# mcu.net
KiCad netlist of a schematic drawn in Altium Designer
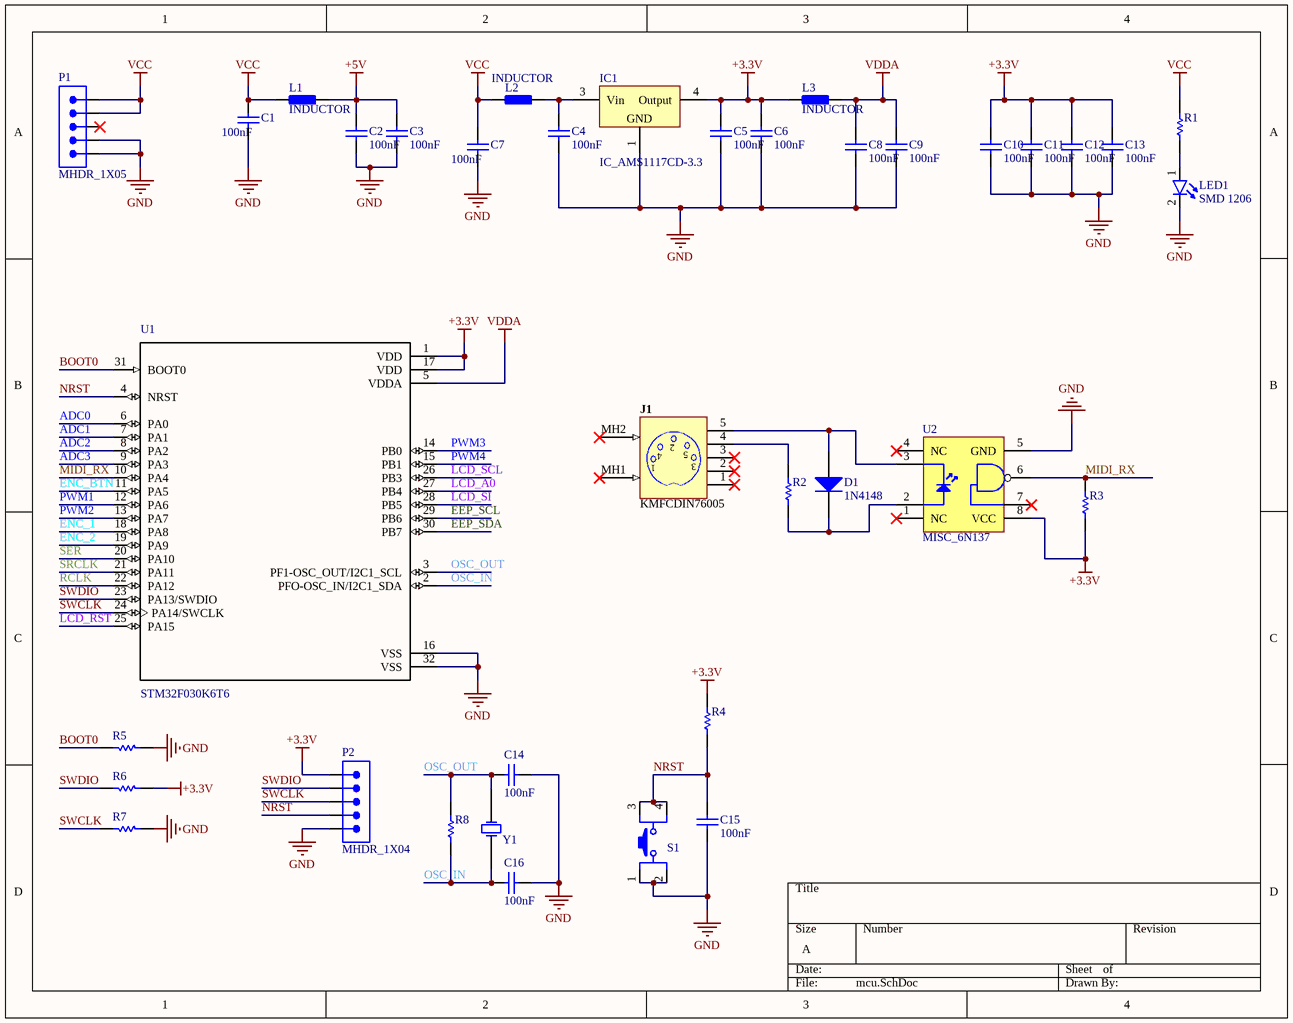
[diagram p0: mcu.SchDoc]

(export (version "E")
  (design (tool "Eeschema 10.0.6"))
  (components
    (comp (ref "C1")
      (value "100nF")
      (footprint "CAPC3216M (1206)")
      (description "Bipolar Capacitor")
      (fields
        (field (name "VOLTAGE") "100V")
        (field (name "DESIGNER") "Eng. Saeid Jorablo")
        (field (name "PUBLISHER") "SJ Unlimited")
      )
      (libsource (lib "SJ Passive Components") (part "CAP_Bipolar"))
    )
    (comp (ref "C2")
      (value "100nF")
      (footprint "CAPC3216M (1206)")
      (description "Bipolar Capacitor")
      (fields
        (field (name "VOLTAGE") "100V")
        (field (name "DESIGNER") "Eng. Saeid Jorablo")
        (field (name "PUBLISHER") "SJ Unlimited")
      )
      (libsource (lib "SJ Passive Components") (part "CAP_Bipolar"))
    )
    (comp (ref "C3")
      (value "100nF")
      (footprint "CAPC3216M (1206)")
      (description "Bipolar Capacitor")
      (fields
        (field (name "VOLTAGE") "100V")
        (field (name "Comment") "1uF")
        (field (name "DESIGNER") "Eng. Saeid Jorablo")
        (field (name "PUBLISHER") "SJ Unlimited")
      )
      (libsource (lib "SJ Passive Components") (part "CAP_Bipolar"))
    )
    (comp (ref "C4")
      (value "100nF")
      (footprint "CAPC3216M (1206)")
      (description "Bipolar Capacitor")
      (fields
        (field (name "VOLTAGE") "100V")
        (field (name "DESIGNER") "Eng. Saeid Jorablo")
        (field (name "PUBLISHER") "SJ Unlimited")
      )
      (libsource (lib "SJ Passive Components") (part "CAP_Bipolar"))
    )
    (comp (ref "C5")
      (value "100nF")
      (footprint "CAPC3216M (1206)")
      (description "Bipolar Capacitor")
      (fields
        (field (name "VOLTAGE") "100V")
        (field (name "DESIGNER") "Eng. Saeid Jorablo")
        (field (name "PUBLISHER") "SJ Unlimited")
      )
      (libsource (lib "SJ Passive Components") (part "CAP_Bipolar"))
    )
    (comp (ref "C6")
      (value "100nF")
      (footprint "CAPC3216M (1206)")
      (description "Bipolar Capacitor")
      (fields
        (field (name "VOLTAGE") "100V")
        (field (name "DESIGNER") "Eng. Saeid Jorablo")
        (field (name "PUBLISHER") "SJ Unlimited")
      )
      (libsource (lib "SJ Passive Components") (part "CAP_Bipolar"))
    )
    (comp (ref "C7")
      (value "100nF")
      (footprint "CAPC3216M (1206)")
      (description "Bipolar Capacitor")
      (fields
        (field (name "VOLTAGE") "100V")
        (field (name "DESIGNER") "Eng. Saeid Jorablo")
        (field (name "PUBLISHER") "SJ Unlimited")
      )
      (libsource (lib "SJ Passive Components") (part "CAP_Bipolar"))
    )
    (comp (ref "C8")
      (value "100nF")
      (footprint "CAPC3216M (1206)")
      (description "Bipolar Capacitor")
      (fields
        (field (name "VOLTAGE") "100V")
        (field (name "DESIGNER") "Eng. Saeid Jorablo")
        (field (name "PUBLISHER") "SJ Unlimited")
      )
      (libsource (lib "SJ Passive Components") (part "CAP_Bipolar"))
    )
    (comp (ref "C9")
      (value "100nF")
      (footprint "CAPC3216M (1206)")
      (description "Bipolar Capacitor")
      (fields
        (field (name "VOLTAGE") "100V")
        (field (name "Comment") "1uF")
        (field (name "DESIGNER") "Eng. Saeid Jorablo")
        (field (name "PUBLISHER") "SJ Unlimited")
      )
      (libsource (lib "SJ Passive Components") (part "CAP_Bipolar"))
    )
    (comp (ref "C10")
      (value "100nF")
      (footprint "CAPC3216M (1206)")
      (description "Bipolar Capacitor")
      (fields
        (field (name "VOLTAGE") "100V")
        (field (name "DESIGNER") "Eng. Saeid Jorablo")
        (field (name "PUBLISHER") "SJ Unlimited")
      )
      (libsource (lib "SJ Passive Components") (part "CAP_Bipolar"))
    )
    (comp (ref "C11")
      (value "100nF")
      (footprint "CAPC3216M (1206)")
      (description "Bipolar Capacitor")
      (fields
        (field (name "VOLTAGE") "100V")
        (field (name "DESIGNER") "Eng. Saeid Jorablo")
        (field (name "PUBLISHER") "SJ Unlimited")
      )
      (libsource (lib "SJ Passive Components") (part "CAP_Bipolar"))
    )
    (comp (ref "C12")
      (value "100nF")
      (footprint "CAPC3216M (1206)")
      (description "Bipolar Capacitor")
      (fields
        (field (name "VOLTAGE") "100V")
        (field (name "DESIGNER") "Eng. Saeid Jorablo")
        (field (name "PUBLISHER") "SJ Unlimited")
      )
      (libsource (lib "SJ Passive Components") (part "CAP_Bipolar"))
    )
    (comp (ref "C13")
      (value "100nF")
      (footprint "CAPC3216M (1206)")
      (description "Bipolar Capacitor")
      (fields
        (field (name "VOLTAGE") "100V")
        (field (name "DESIGNER") "Eng. Saeid Jorablo")
        (field (name "PUBLISHER") "SJ Unlimited")
      )
      (libsource (lib "SJ Passive Components") (part "CAP_Bipolar"))
    )
    (comp (ref "C14")
      (value "100nF")
      (footprint "CAPC3216M (1206)")
      (description "Bipolar Capacitor")
      (fields
        (field (name "VOLTAGE") "100V")
        (field (name "DESIGNER") "Eng. Saeid Jorablo")
        (field (name "PUBLISHER") "SJ Unlimited")
      )
      (libsource (lib "SJ Passive Components") (part "CAP_Bipolar"))
    )
    (comp (ref "C15")
      (value "100nF")
      (footprint "CAPC3216M (1206)")
      (description "Bipolar Capacitor")
      (fields
        (field (name "VOLTAGE") "100V")
        (field (name "DESIGNER") "Eng. Saeid Jorablo")
        (field (name "PUBLISHER") "SJ Unlimited")
      )
      (libsource (lib "SJ Passive Components") (part "CAP_Bipolar"))
    )
    (comp (ref "C16")
      (value "100nF")
      (footprint "CAPC3216M (1206)")
      (description "Bipolar Capacitor")
      (fields
        (field (name "VOLTAGE") "100V")
        (field (name "DESIGNER") "Eng. Saeid Jorablo")
        (field (name "PUBLISHER") "SJ Unlimited")
      )
      (libsource (lib "SJ Passive Components") (part "CAP_Bipolar"))
    )
    (comp (ref "D1")
      (value "1N4148")
      (footprint "LL4148")
      (description "High Conductance Fast Diode")
      (fields (field (name "PUBLISHER") "SJ Unlimited") (field (name "DESIGNER") "Eng. Saeid Jorablo"))
      (libsource (lib "SJ Passive Components") (part "DIODE_1N4148"))
    )
    (comp (ref "IC1")
      (value "IC_AMS1117CD-3.3")
      (footprint "TO252-3M")
      (description "800mA LOW DROPOUT VOLTAGE REGULATOR")
      (fields
        (field (name "MANUFACTURER") "Advanced Monolithic Systems, Inc.")
        (field (name "DESIGNER") "Eng. Saeid Jorablo")
      )
      (libsource (lib "SJ Altium Library") (part "IC_AMS1117CD-3.3"))
    )
    (comp (ref "J1")
      (value "KMFCDIN76005")
      (footprint "DIP_CON_DIN5")
      (description "Socket, 5-way R/A DIN")
      (fields (field (name "DESIGNER") "Eng. Saeid Jorablo") (field (name "PUBLISHER") "SJ UnLimited"))
      (libsource (lib "SJ Sockets & Connectors") (part "CON_DIN5"))
    )
    (comp (ref "L1")
      (value "INDUCTOR")
      (footprint "INDC4532")
      (description "Inductor")
      (fields (field (name "PUBLISHER") "SJ Unlimited") (field (name "DESIGNER") "Eng. Saeid Jorablo"))
      (libsource (lib "SJ Passive Components") (part "INDUCTOR"))
    )
    (comp (ref "L2")
      (value "INDUCTOR")
      (footprint "INDC4532")
      (description "Inductor")
      (fields (field (name "PUBLISHER") "SJ Unlimited") (field (name "DESIGNER") "Eng. Saeid Jorablo"))
      (libsource (lib "SJ Passive Components") (part "INDUCTOR"))
    )
    (comp (ref "L3")
      (value "INDUCTOR")
      (footprint "INDC4532")
      (description "Inductor")
      (fields (field (name "PUBLISHER") "SJ Unlimited") (field (name "DESIGNER") "Eng. Saeid Jorablo"))
      (libsource (lib "SJ Passive Components") (part "INDUCTOR"))
    )
    (comp (ref "LED1")
      (value "Red")
      (footprint "LED SMD 1206")
      (description "LED")
      (fields
        (field (name "SIZE") "SMD 1206")
        (field (name "DESIGNER") "Eng. Saeid Jorablo")
        (field (name "PUBLISHER") "SJ Unlimited")
      )
      (libsource (lib "SJ Passive Components") (part "LED"))
    )
    (comp (ref "P1")
      (value "MHDR_1X05")
      (footprint "MHDR1X05-254P")
      (description "Male Header 1X05")
      (libsource (lib "") (part "MHDR_1X05_1"))
    )
    (comp (ref "P2")
      (value "MHDR_1X04")
      (footprint "MHDR1X04-254P")
      (description "Male Header 1X05")
      (libsource (lib "SJ Sockets & Connectors") (part "MHDR_1X05"))
    )
    (comp (ref "R1")
      (value "1K")
      (footprint "RESC3216X60M (1206)")
      (description "Resistor")
      (fields
        (field (name "TOLERANCE") "5%")
        (field (name "POWER") "1/8 W")
        (field (name "DESIGNER") "Eng. Saeid Jorablo")
        (field (name "PUBLISHER") "SJ Unlimited")
      )
      (libsource (lib "SJ Passive Components") (part "RES"))
    )
    (comp (ref "R2")
      (value "1K")
      (footprint "RESC3216X60M (1206)")
      (description "Resistor")
      (fields
        (field (name "TOLERANCE") "5%")
        (field (name "POWER") "1/8 W")
        (field (name "DESIGNER") "Eng. Saeid Jorablo")
        (field (name "PUBLISHER") "SJ Unlimited")
      )
      (libsource (lib "SJ Passive Components") (part "RES"))
    )
    (comp (ref "R3")
      (value "1K")
      (footprint "RESC3216X60M (1206)")
      (description "Resistor")
      (fields
        (field (name "TOLERANCE") "5%")
        (field (name "POWER") "1/8 W")
        (field (name "DESIGNER") "Eng. Saeid Jorablo")
        (field (name "PUBLISHER") "SJ Unlimited")
      )
      (libsource (lib "SJ Passive Components") (part "RES"))
    )
    (comp (ref "R4")
      (value "1K")
      (footprint "RESC3216X60M (1206)")
      (description "Resistor")
      (fields
        (field (name "TOLERANCE") "5%")
        (field (name "POWER") "1/8 W")
        (field (name "DESIGNER") "Eng. Saeid Jorablo")
        (field (name "PUBLISHER") "SJ Unlimited")
      )
      (libsource (lib "SJ Passive Components") (part "RES"))
    )
    (comp (ref "R5")
      (value "1K")
      (footprint "RESC2012M (0805)")
      (description "Resistor")
      (fields
        (field (name "TOLERANCE") "5%")
        (field (name "POWER") "1/8 W")
        (field (name "DESIGNER") "Eng. Saeid Jorablo")
        (field (name "PUBLISHER") "SJ Unlimited")
      )
      (libsource (lib "SJ Passive Components") (part "RES"))
    )
    (comp (ref "R6")
      (value "1K")
      (footprint "RESC3216X60M (1206)")
      (description "Resistor")
      (fields
        (field (name "TOLERANCE") "5%")
        (field (name "POWER") "1/8 W")
        (field (name "DESIGNER") "Eng. Saeid Jorablo")
        (field (name "PUBLISHER") "SJ Unlimited")
      )
      (libsource (lib "SJ Passive Components") (part "RES"))
    )
    (comp (ref "R7")
      (value "1K")
      (footprint "RESC3216X60M (1206)")
      (description "Resistor")
      (fields
        (field (name "TOLERANCE") "5%")
        (field (name "POWER") "1/8 W")
        (field (name "DESIGNER") "Eng. Saeid Jorablo")
        (field (name "PUBLISHER") "SJ Unlimited")
      )
      (libsource (lib "SJ Passive Components") (part "RES"))
    )
    (comp (ref "R8")
      (value "1K")
      (footprint "RESC3216X60M (1206)")
      (description "Resistor")
      (fields
        (field (name "TOLERANCE") "5%")
        (field (name "POWER") "1/8 W")
        (field (name "DESIGNER") "Eng. Saeid Jorablo")
        (field (name "PUBLISHER") "SJ Unlimited")
      )
      (libsource (lib "SJ Passive Components") (part "RES"))
    )
    (comp (ref "S1")
      (value "SW_PB4A")
      (footprint "THT_ALPS_SKHHBVA010")
      (description "4 Pin Push Button Switch")
      (fields (field (name "DESIGNER") "Eng. Saeid Jorablo"))
      (libsource (lib "SJ Switches") (part "SW_PB4A"))
    )
    (comp (ref "U1")
      (value "STM32F030K6T6")
      (footprint "*QFP80P900X900X160-32N")
      (description "MCU 32-Bit STM32F ARM Cortex M0 RISC 32KB Flash 2.5V/3.3V 32-Pin LQFP Tray")
      (fields (field (name "MF") "STMicroelectronics"))
      (libsource (lib "STM32F030K6T6") (part "STM32F030K6T6"))
    )
    (comp (ref "U2")
      (value "MISC_6N137")
      (footprint "CDIP8")
      (description "HIGH SPEED-10 MBit/s  LOGIC GATE OPTOCOUPLERS")
      (fields (field (name "DESIGNER") "Eng. Saeid Jorablo"))
      (libsource (lib "SJ Altium Library") (part "MISC_6N137"))
    )
    (comp (ref "Y1")
      (value "11.0592 MHz")
      (footprint "XTAL")
      (description "XTAL Crystal")
      (fields (field (name "DESIGNER") "Eng. Saeid Jorablo") (field (name "PUBLISHER") "SJ Unlimited"))
      (libsource (lib "SJ Passive Components") (part "XTAL_Crystal"))
    )
  )
  (nets
    (net (code "1") (name "+3.3V") (class "Default")
      (node (ref "C10") (pin "1") (pinfunction "+_1") (pintype "passive"))
      (node (ref "C11") (pin "1") (pinfunction "+_1") (pintype "passive"))
      (node (ref "C12") (pin "1") (pinfunction "+_1") (pintype "passive"))
      (node (ref "C13") (pin "1") (pinfunction "+_1") (pintype "passive"))
      (node (ref "C5") (pin "1") (pinfunction "+_1") (pintype "passive"))
      (node (ref "C6") (pin "1") (pinfunction "+_1") (pintype "passive"))
      (node (ref "IC1") (pin "4") (pinfunction "Output_4") (pintype "passive"))
      (node (ref "L3") (pin "1") (pinfunction "1_1") (pintype "passive"))
      (node (ref "P2") (pin "1") (pinfunction "1_1") (pintype "passive"))
      (node (ref "R3") (pin "1") (pinfunction "1_1") (pintype "passive"))
      (node (ref "R4") (pin "2") (pinfunction "2_2") (pintype "passive"))
      (node (ref "R6") (pin "2") (pinfunction "2_2") (pintype "passive"))
      (node (ref "U1") (pin "1") (pinfunction "VDD_1") (pintype "power_in"))
      (node (ref "U1") (pin "17") (pinfunction "VDD_17") (pintype "power_in"))
      (node (ref "U2") (pin "8") (pinfunction "VCC_8") (pintype "passive"))
    )
    (net (code "2") (name "+5V") (class "Default")
      (node (ref "C2") (pin "1") (pinfunction "+_1") (pintype "passive"))
      (node (ref "C3") (pin "1") (pinfunction "+_1") (pintype "passive"))
      (node (ref "L1") (pin "2") (pinfunction "2_2") (pintype "passive"))
    )
    (net (code "3") (name "/ADC0") (class "Default")
      (node (ref "U1") (pin "6") (pinfunction "PA0_6") (pintype "bidirectional"))
    )
    (net (code "4") (name "/ADC1") (class "Default")
      (node (ref "U1") (pin "7") (pinfunction "PA1_7") (pintype "bidirectional"))
    )
    (net (code "5") (name "/ADC2") (class "Default")
      (node (ref "U1") (pin "8") (pinfunction "PA2_8") (pintype "bidirectional"))
    )
    (net (code "6") (name "/ADC3") (class "Default")
      (node (ref "U1") (pin "9") (pinfunction "PA3_9") (pintype "bidirectional"))
    )
    (net (code "7") (name "/BOOT0") (class "Default")
      (node (ref "R5") (pin "1") (pinfunction "1_1") (pintype "passive"))
      (node (ref "U1") (pin "31") (pinfunction "BOOT0_31") (pintype "input"))
    )
    (net (code "8") (name "/EEP_SCL") (class "Default")
      (node (ref "U1") (pin "29") (pinfunction "PB6_29") (pintype "bidirectional"))
    )
    (net (code "9") (name "/EEP_SDA") (class "Default")
      (node (ref "U1") (pin "30") (pinfunction "PB7_30") (pintype "bidirectional"))
    )
    (net (code "10") (name "/ENC_1") (class "Default")
      (node (ref "U1") (pin "18") (pinfunction "PA8_18") (pintype "bidirectional"))
    )
    (net (code "11") (name "/ENC_2") (class "Default")
      (node (ref "U1") (pin "19") (pinfunction "PA9_19") (pintype "bidirectional"))
    )
    (net (code "12") (name "/ENC_BTN") (class "Default")
      (node (ref "U1") (pin "11") (pinfunction "PA5_11") (pintype "bidirectional"))
    )
    (net (code "13") (name "/LCD_A0") (class "Default")
      (node (ref "U1") (pin "27") (pinfunction "PB4_27") (pintype "bidirectional"))
    )
    (net (code "14") (name "/LCD_RST") (class "Default")
      (node (ref "U1") (pin "25") (pinfunction "PA15_25") (pintype "bidirectional"))
    )
    (net (code "15") (name "/LCD_SCL") (class "Default")
      (node (ref "U1") (pin "26") (pinfunction "PB3_26") (pintype "bidirectional"))
    )
    (net (code "16") (name "/LCD_SI") (class "Default")
      (node (ref "U1") (pin "28") (pinfunction "PB5_28") (pintype "bidirectional"))
    )
    (net (code "17") (name "/MIDI_RX") (class "Default")
      (node (ref "R3") (pin "2") (pinfunction "2_2") (pintype "passive"))
      (node (ref "U1") (pin "10") (pinfunction "PA4_10") (pintype "bidirectional"))
      (node (ref "U2") (pin "6") (pinfunction "Vo_6") (pintype "passive"))
    )
    (net (code "18") (name "/NRST") (class "Default")
      (node (ref "C15") (pin "1") (pinfunction "+_1") (pintype "passive"))
      (node (ref "P2") (pin "4") (pinfunction "4_4") (pintype "passive"))
      (node (ref "R4") (pin "1") (pinfunction "1_1") (pintype "passive"))
      (node (ref "S1") (pin "3") (pinfunction "3_3") (pintype "passive"))
      (node (ref "S1") (pin "4") (pinfunction "4_4") (pintype "passive"))
      (node (ref "U1") (pin "4") (pinfunction "NRST_4") (pintype "bidirectional"))
    )
    (net (code "19") (name "/OSC_IN") (class "Default")
      (node (ref "C16") (pin "1") (pinfunction "+_1") (pintype "passive"))
      (node (ref "R8") (pin "1") (pinfunction "1_1") (pintype "passive"))
      (node (ref "U1") (pin "2") (pinfunction "PFO-OSC_IN/I2C1_SDA_2") (pintype "bidirectional"))
      (node (ref "Y1") (pin "2") (pinfunction "OSC2_2") (pintype "passive"))
    )
    (net (code "20") (name "/OSC_OUT") (class "Default")
      (node (ref "C14") (pin "2") (pinfunction "-_2") (pintype "passive"))
      (node (ref "R8") (pin "2") (pinfunction "2_2") (pintype "passive"))
      (node (ref "U1") (pin "3") (pinfunction "PF1-OSC_OUT/I2C1_SCL_3") (pintype "bidirectional"))
      (node (ref "Y1") (pin "1") (pinfunction "OSC1_1") (pintype "passive"))
    )
    (net (code "21") (name "/PWM1") (class "Default")
      (node (ref "U1") (pin "12") (pinfunction "PA6_12") (pintype "bidirectional"))
    )
    (net (code "22") (name "/PWM2") (class "Default")
      (node (ref "U1") (pin "13") (pinfunction "PA7_13") (pintype "bidirectional"))
    )
    (net (code "23") (name "/PWM3") (class "Default")
      (node (ref "U1") (pin "14") (pinfunction "PB0_14") (pintype "bidirectional"))
    )
    (net (code "24") (name "/PWM4") (class "Default")
      (node (ref "U1") (pin "15") (pinfunction "PB1_15") (pintype "bidirectional"))
    )
    (net (code "25") (name "/RCLK") (class "Default")
      (node (ref "U1") (pin "22") (pinfunction "PA12_22") (pintype "bidirectional"))
    )
    (net (code "26") (name "/SER") (class "Default")
      (node (ref "U1") (pin "20") (pinfunction "PA10_20") (pintype "bidirectional"))
    )
    (net (code "27") (name "/SRCLK") (class "Default")
      (node (ref "U1") (pin "21") (pinfunction "PA11_21") (pintype "bidirectional"))
    )
    (net (code "28") (name "/SWCLK") (class "Default")
      (node (ref "P2") (pin "3") (pinfunction "3_3") (pintype "passive"))
      (node (ref "R7") (pin "1") (pinfunction "1_1") (pintype "passive"))
      (node (ref "U1") (pin "24") (pinfunction "PA14/SWCLK_24") (pintype "bidirectional"))
    )
    (net (code "29") (name "/SWDIO") (class "Default")
      (node (ref "P2") (pin "2") (pinfunction "2_2") (pintype "passive"))
      (node (ref "R6") (pin "1") (pinfunction "1_1") (pintype "passive"))
      (node (ref "U1") (pin "23") (pinfunction "PA13/SWDIO_23") (pintype "bidirectional"))
    )
    (net (code "30") (name "GND") (class "Default")
      (node (ref "C1") (pin "2") (pinfunction "-_2") (pintype "passive"))
      (node (ref "C10") (pin "2") (pinfunction "-_2") (pintype "passive"))
      (node (ref "C11") (pin "2") (pinfunction "-_2") (pintype "passive"))
      (node (ref "C12") (pin "2") (pinfunction "-_2") (pintype "passive"))
      (node (ref "C13") (pin "2") (pinfunction "-_2") (pintype "passive"))
      (node (ref "C14") (pin "1") (pinfunction "+_1") (pintype "passive"))
      (node (ref "C15") (pin "2") (pinfunction "-_2") (pintype "passive"))
      (node (ref "C16") (pin "2") (pinfunction "-_2") (pintype "passive"))
      (node (ref "C2") (pin "2") (pinfunction "-_2") (pintype "passive"))
      (node (ref "C3") (pin "2") (pinfunction "-_2") (pintype "passive"))
      (node (ref "C4") (pin "2") (pinfunction "-_2") (pintype "passive"))
      (node (ref "C5") (pin "2") (pinfunction "-_2") (pintype "passive"))
      (node (ref "C6") (pin "2") (pinfunction "-_2") (pintype "passive"))
      (node (ref "C7") (pin "2") (pinfunction "-_2") (pintype "passive"))
      (node (ref "C8") (pin "2") (pinfunction "-_2") (pintype "passive"))
      (node (ref "C9") (pin "2") (pinfunction "-_2") (pintype "passive"))
      (node (ref "IC1") (pin "1") (pinfunction "GND_1") (pintype "passive"))
      (node (ref "LED1") (pin "2") (pinfunction "K_2") (pintype "passive"))
      (node (ref "P1") (pin "4") (pinfunction "4_4") (pintype "passive"))
      (node (ref "P1") (pin "5") (pinfunction "5_5") (pintype "passive"))
      (node (ref "P2") (pin "4") (pinfunction "4_4") (pintype "passive"))
      (node (ref "R5") (pin "2") (pinfunction "2_2") (pintype "passive"))
      (node (ref "R7") (pin "2") (pinfunction "2_2") (pintype "passive"))
      (node (ref "S1") (pin "1") (pinfunction "1_1") (pintype "passive"))
      (node (ref "S1") (pin "2") (pinfunction "2_2") (pintype "passive"))
      (node (ref "U1") (pin "16") (pinfunction "VSS_16") (pintype "power_in"))
      (node (ref "U1") (pin "32") (pinfunction "VSS_32") (pintype "power_in"))
      (node (ref "U2") (pin "5") (pinfunction "GND_5") (pintype "passive"))
    )
    (net (code "31") (name "Net-(C4-+)") (class "Default")
      (node (ref "C4") (pin "1") (pinfunction "+_1") (pintype "passive"))
      (node (ref "IC1") (pin "3") (pinfunction "Vin_3") (pintype "passive"))
      (node (ref "L2") (pin "2") (pinfunction "2_2") (pintype "passive"))
    )
    (net (code "32") (name "Net-(D1-A)") (class "Default")
      (node (ref "D1") (pin "1") (pinfunction "A_1") (pintype "passive"))
      (node (ref "J1") (pin "5") (pinfunction "5_5") (pintype "passive"))
      (node (ref "U2") (pin "3") (pinfunction "K_3") (pintype "passive"))
    )
    (net (code "33") (name "Net-(D1-K)") (class "Default")
      (node (ref "D1") (pin "2") (pinfunction "K_2") (pintype "passive"))
      (node (ref "R2") (pin "2") (pinfunction "2_2") (pintype "passive"))
      (node (ref "U2") (pin "2") (pinfunction "A_2") (pintype "passive"))
    )
    (net (code "34") (name "Net-(J1-Pad4)") (class "Default")
      (node (ref "J1") (pin "4") (pinfunction "4_4") (pintype "passive"))
      (node (ref "R2") (pin "1") (pinfunction "1_1") (pintype "passive"))
    )
    (net (code "35") (name "Net-(LED1-A)") (class "Default")
      (node (ref "LED1") (pin "1") (pinfunction "A_1") (pintype "passive"))
      (node (ref "R1") (pin "1") (pinfunction "1_1") (pintype "passive"))
    )
    (net (code "36") (name "VCC") (class "Default")
      (node (ref "C1") (pin "1") (pinfunction "+_1") (pintype "passive"))
      (node (ref "C7") (pin "1") (pinfunction "+_1") (pintype "passive"))
      (node (ref "L1") (pin "1") (pinfunction "1_1") (pintype "passive"))
      (node (ref "L2") (pin "1") (pinfunction "1_1") (pintype "passive"))
      (node (ref "P1") (pin "1") (pinfunction "1_1") (pintype "passive"))
      (node (ref "P1") (pin "2") (pinfunction "2_2") (pintype "passive"))
      (node (ref "R1") (pin "2") (pinfunction "2_2") (pintype "passive"))
    )
    (net (code "37") (name "VDDA") (class "Default")
      (node (ref "C8") (pin "1") (pinfunction "+_1") (pintype "passive"))
      (node (ref "C9") (pin "1") (pinfunction "+_1") (pintype "passive"))
      (node (ref "L3") (pin "2") (pinfunction "2_2") (pintype "passive"))
      (node (ref "U1") (pin "5") (pinfunction "VDDA_5") (pintype "power_in"))
    )
    (net (code "38") (name "unconnected-(J1-Pad1)") (class "Default")
      (node (ref "J1") (pin "1") (pinfunction "1_1") (pintype "passive+no_connect"))
    )
    (net (code "39") (name "unconnected-(J1-Pad2)") (class "Default")
      (node (ref "J1") (pin "2") (pinfunction "2_2") (pintype "passive+no_connect"))
    )
    (net (code "40") (name "unconnected-(J1-Pad3)") (class "Default")
      (node (ref "J1") (pin "3") (pinfunction "3_3") (pintype "passive+no_connect"))
    )
    (net (code "41") (name "unconnected-(J1-PadMH1)") (class "Default")
      (node (ref "J1") (pin "MH1") (pinfunction "MH1_MH1") (pintype "input+no_connect"))
    )
    (net (code "42") (name "unconnected-(J1-PadMH2)") (class "Default")
      (node (ref "J1") (pin "MH2") (pinfunction "MH2_MH2") (pintype "input+no_connect"))
    )
    (net (code "43") (name "unconnected-(P1-Pad3)") (class "Default")
      (node (ref "P1") (pin "3") (pinfunction "3_3") (pintype "passive+no_connect"))
    )
    (net (code "44") (name "unconnected-(U2-NC-Pad1)") (class "Default")
      (node (ref "U2") (pin "1") (pinfunction "NC_1") (pintype "passive+no_connect"))
    )
    (net (code "45") (name "unconnected-(U2-NC-Pad4)") (class "Default")
      (node (ref "U2") (pin "4") (pinfunction "NC_4") (pintype "passive+no_connect"))
    )
    (net (code "46") (name "unconnected-(U2-Ve-Pad7)") (class "Default")
      (node (ref "U2") (pin "7") (pinfunction "Ve_7") (pintype "passive+no_connect"))
    )
  )
)
